# Debug_Interface.net
KiCad netlist of a schematic drawn in Altium Designer
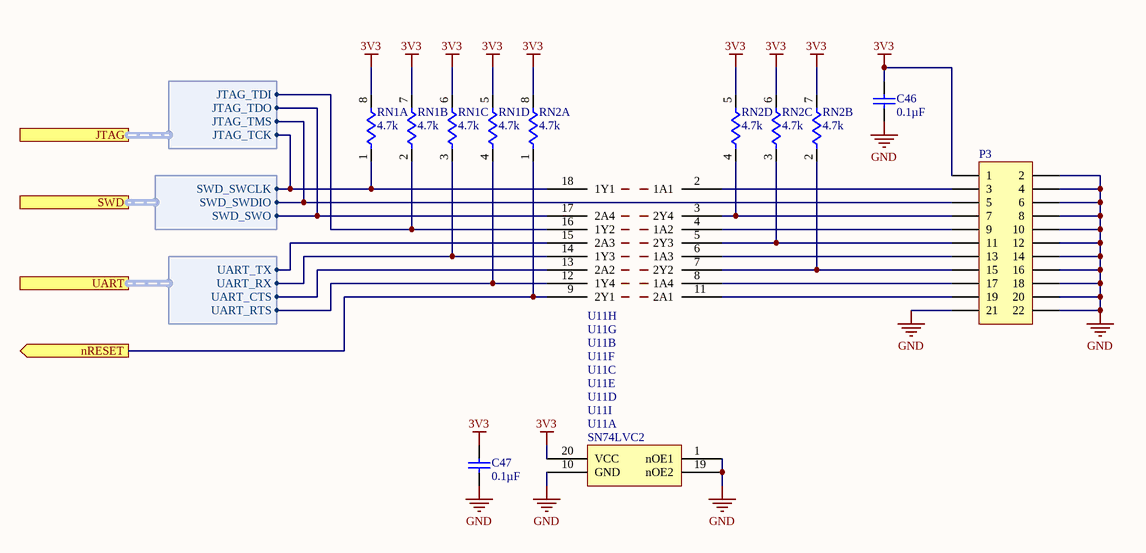
[diagram p0: Debug Interface.SchDoc]

(export (version "E")
  (design (tool "Eeschema 10.0.6"))
  (components
    (comp (ref "C46")
      (value "0.1µF")
      (footprint "TDK-CGA2B")
      (description "CAP CER 0.1UF 50V X7R 0402")
      (fields
        (field (name "PART NUMBER") "PC-TDK-02259")
        (field (name "MANUFACTURER PART NUMBER") "CGA2B3X7R1H104K050BB")
        (field (name "PUBLISHER") "AlbertaSat")
      )
      (libsource (lib "Database") (part "Cap"))
    )
    (comp (ref "C47")
      (value "0.1µF")
      (footprint "TDK-CGA2B")
      (description "CAP CER 0.1UF 50V X7R 0402")
      (fields
        (field (name "PART NUMBER") "PC-TDK-02259")
        (field (name "MANUFACTURER PART NUMBER") "CGA2B3X7R1H104K050BB")
        (field (name "PUBLISHER") "AlbertaSat")
      )
      (libsource (lib "Database") (part "Cap"))
    )
    (comp (ref "P3")
      (value "G125-MH12005L1P")
      (footprint "HWN-G125-MH12005L1P")
      (description "CONN HEADER R/A 20POS 1.25MM")
      (fields (field (name "PART NUMBER") "PP-HWN-00018") (field (name "PUBLISHER") "AlbertaSat"))
      (libsource (lib "Database") (part "Header 11X2"))
    )
    (comp (ref "RN1")
      (value "4.7k")
      (footprint "PANA-EXB28V")
      (description "RES ARRAY 4 RES 4.7K OHM 0804")
      (fields (field (name "PART NUMBER") "19961") (field (name "MANUFACTURER PART NUMBER") "EXB-28V472JX"))
      (libsource (lib "Database") (part "Res4 Pack1"))
    )
    (comp (ref "RN2")
      (value "4.7k")
      (footprint "PANA-EXB28V")
      (description "RES ARRAY 4 RES 4.7K OHM 0804")
      (fields (field (name "PART NUMBER") "19961") (field (name "MANUFACTURER PART NUMBER") "EXB-28V472JX"))
      (libsource (lib "Database") (part "Res4 Pack1"))
    )
    (comp (ref "U11")
      (value "SN74LVC2")
      (footprint "TI-PWRPDSOG20")
      (description "IC BUF NON-INVERT 3.6V 20TSSOP")
      (fields (field (name "PART NUMBER") "53") (field (name "MANUFACTURER PART NUMBER") "SN74LVC244APWR"))
      (libsource (lib "") (part "SN74LVC244APWR_1"))
    )
  )
  (nets
    (net (code "4") (name "/JTAG_TCK") (class "Default")
      (node (ref "RN1") (pin "1") (pinfunction "1_1") (pintype "passive"))
      (node (ref "U11") (pin "18") (pinfunction "1Y1_18") (pintype "passive"))
    )
    (net (code "5") (name "/JTAG_TDI") (class "Default")
      (node (ref "RN1") (pin "2") (pinfunction "2_2") (pintype "passive"))
      (node (ref "U11") (pin "16") (pinfunction "1Y2_16") (pintype "passive"))
    )
    (net (code "6") (name "/JTAG_TDO") (class "Default")
      (node (ref "U11") (pin "17") (pinfunction "2A4_17") (pintype "passive"))
    )
    (net (code "7") (name "/JTAG_TMS") (class "Default")
      (node (ref "P3") (pin "5") (pinfunction "5_5") (pintype "passive"))
    )
    (net (code "8") (name "/UART_CTS") (class "Default")
      (node (ref "U11") (pin "13") (pinfunction "2A2_13") (pintype "passive"))
    )
    (net (code "9") (name "/UART_RTS") (class "Default")
      (node (ref "RN1") (pin "4") (pinfunction "4_4") (pintype "passive"))
      (node (ref "U11") (pin "12") (pinfunction "1Y4_12") (pintype "passive"))
    )
    (net (code "10") (name "/UART_RX") (class "Default")
      (node (ref "RN1") (pin "3") (pinfunction "3_3") (pintype "passive"))
      (node (ref "U11") (pin "14") (pinfunction "1Y3_14") (pintype "passive"))
    )
    (net (code "11") (name "/UART_TX") (class "Default")
      (node (ref "U11") (pin "15") (pinfunction "2A3_15") (pintype "passive"))
    )
    (net (code "12") (name "/nRESET") (class "Default")
      (node (ref "RN2") (pin "1") (pinfunction "1_1") (pintype "passive"))
      (node (ref "U11") (pin "9") (pinfunction "2Y1_9") (pintype "passive"))
    )
    (net (code "16") (name "3V3") (class "Default")
      (node (ref "C46") (pin "1") (pinfunction "1_1") (pintype "passive"))
      (node (ref "C47") (pin "1") (pinfunction "1_1") (pintype "passive"))
      (node (ref "P3") (pin "1") (pinfunction "1_1") (pintype "passive"))
      (node (ref "RN1") (pin "5") (pinfunction "5_5") (pintype "passive"))
      (node (ref "RN1") (pin "6") (pinfunction "6_6") (pintype "passive"))
      (node (ref "RN1") (pin "7") (pinfunction "7_7") (pintype "passive"))
      (node (ref "RN1") (pin "8") (pinfunction "8_8") (pintype "passive"))
      (node (ref "RN2") (pin "5") (pinfunction "5_5") (pintype "passive"))
      (node (ref "RN2") (pin "6") (pinfunction "6_6") (pintype "passive"))
      (node (ref "RN2") (pin "7") (pinfunction "7_7") (pintype "passive"))
      (node (ref "RN2") (pin "8") (pinfunction "8_8") (pintype "passive"))
      (node (ref "U11") (pin "20") (pinfunction "VCC_20") (pintype "passive"))
    )
    (net (code "17") (name "GND") (class "Default")
      (node (ref "C46") (pin "2") (pinfunction "2_2") (pintype "passive"))
      (node (ref "C47") (pin "2") (pinfunction "2_2") (pintype "passive"))
      (node (ref "P3") (pin "10") (pinfunction "10_10") (pintype "passive"))
      (node (ref "P3") (pin "12") (pinfunction "12_12") (pintype "passive"))
      (node (ref "P3") (pin "14") (pinfunction "14_14") (pintype "passive"))
      (node (ref "P3") (pin "16") (pinfunction "16_16") (pintype "passive"))
      (node (ref "P3") (pin "18") (pinfunction "18_18") (pintype "passive"))
      (node (ref "P3") (pin "2") (pinfunction "2_2") (pintype "passive"))
      (node (ref "P3") (pin "20") (pinfunction "20_20") (pintype "passive"))
      (node (ref "P3") (pin "21") (pinfunction "21_21") (pintype "passive"))
      (node (ref "P3") (pin "22") (pinfunction "22_22") (pintype "passive"))
      (node (ref "P3") (pin "4") (pinfunction "4_4") (pintype "passive"))
      (node (ref "P3") (pin "6") (pinfunction "6_6") (pintype "passive"))
      (node (ref "P3") (pin "8") (pinfunction "8_8") (pintype "passive"))
      (node (ref "U11") (pin "1") (pinfunction "nOE1_1") (pintype "passive"))
      (node (ref "U11") (pin "10") (pinfunction "GND_10") (pintype "passive"))
      (node (ref "U11") (pin "19") (pinfunction "nOE2_19") (pintype "passive"))
    )
    (net (code "18") (name "Net-(U11B-1A2)") (class "Default")
      (node (ref "P3") (pin "9") (pinfunction "9_9") (pintype "passive"))
      (node (ref "U11") (pin "4") (pinfunction "1A2_4") (pintype "passive"))
    )
    (net (code "19") (name "Net-(U11C-1A3)") (class "Default")
      (node (ref "P3") (pin "13") (pinfunction "13_13") (pintype "passive"))
      (node (ref "U11") (pin "6") (pinfunction "1A3_6") (pintype "passive"))
    )
    (net (code "20") (name "Net-(U11D-1A4)") (class "Default")
      (node (ref "P3") (pin "17") (pinfunction "17_17") (pintype "passive"))
      (node (ref "U11") (pin "8") (pinfunction "1A4_8") (pintype "passive"))
    )
    (net (code "21") (name "Net-(U11E-2Y2)") (class "Default")
      (node (ref "P3") (pin "15") (pinfunction "15_15") (pintype "passive"))
      (node (ref "RN2") (pin "2") (pinfunction "2_2") (pintype "passive"))
      (node (ref "U11") (pin "7") (pinfunction "2Y2_7") (pintype "passive"))
    )
    (net (code "22") (name "Net-(U11F-2Y3)") (class "Default")
      (node (ref "P3") (pin "11") (pinfunction "11_11") (pintype "passive"))
      (node (ref "RN2") (pin "3") (pinfunction "3_3") (pintype "passive"))
      (node (ref "U11") (pin "5") (pinfunction "2Y3_5") (pintype "passive"))
    )
    (net (code "23") (name "Net-(U11G-2Y4)") (class "Default")
      (node (ref "P3") (pin "7") (pinfunction "7_7") (pintype "passive"))
      (node (ref "RN2") (pin "4") (pinfunction "4_4") (pintype "passive"))
      (node (ref "U11") (pin "3") (pinfunction "2Y4_3") (pintype "passive"))
    )
    (net (code "24") (name "Net-(U11H-1A1)") (class "Default")
      (node (ref "P3") (pin "3") (pinfunction "3_3") (pintype "passive"))
      (node (ref "U11") (pin "2") (pinfunction "1A1_2") (pintype "passive"))
    )
    (net (code "25") (name "Net-(U11I-2A1)") (class "Default")
      (node (ref "P3") (pin "19") (pinfunction "19_19") (pintype "passive"))
      (node (ref "U11") (pin "11") (pinfunction "2A1_11") (pintype "passive"))
    )
  )
)
